# CON_ETHERNET_RJ45_LEDS.net
KiCad netlist of a schematic drawn in Altium Designer
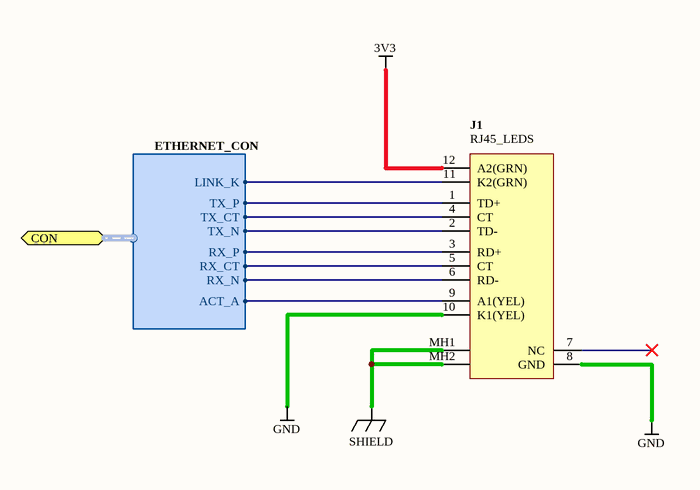
[diagram p0: CON_ETHERNET_RJ45_LEDS.SchDoc]

(export (version "E")
  (design (tool "Eeschema 10.0.6"))
  (components
    (comp (ref "J1")
      (value "RJ45_LEDS")
      (footprint "CON_RJ45_RA_LEDS")
      (description "Socket, 1x1 Tab-DOWN R/A 8-Way RJ45")
      (libsource (lib "AltiumDesignLibrary") (part "CON_RJ45_RA_LEDS"))
    )
  )
  (nets
    (net (code "2") (name "/ACT_A") (class "Default")
      (node (ref "J1") (pin "9") (pinfunction "A1(YEL)_9") (pintype "passive"))
    )
    (net (code "3") (name "/LINK_K") (class "Default")
      (node (ref "J1") (pin "11") (pinfunction "K2(GRN)_11") (pintype "passive"))
    )
    (net (code "4") (name "/RX_CT") (class "Default")
      (node (ref "J1") (pin "5") (pinfunction "CT_5") (pintype "passive"))
    )
    (net (code "5") (name "/RX_N") (class "Default")
      (node (ref "J1") (pin "6") (pinfunction "RD-_6") (pintype "passive"))
    )
    (net (code "6") (name "/RX_P") (class "Default")
      (node (ref "J1") (pin "3") (pinfunction "RD+_3") (pintype "passive"))
    )
    (net (code "7") (name "/TX_CT") (class "Default")
      (node (ref "J1") (pin "4") (pinfunction "CT_4") (pintype "passive"))
    )
    (net (code "8") (name "/TX_N") (class "Default")
      (node (ref "J1") (pin "2") (pinfunction "TD-_2") (pintype "passive"))
    )
    (net (code "9") (name "/TX_P") (class "Default")
      (node (ref "J1") (pin "1") (pinfunction "TD+_1") (pintype "passive"))
    )
    (net (code "11") (name "3V3") (class "Default")
      (node (ref "J1") (pin "12") (pinfunction "A2(GRN)_12") (pintype "passive"))
    )
    (net (code "12") (name "GND") (class "Default")
      (node (ref "J1") (pin "10") (pinfunction "K1(YEL)_10") (pintype "passive"))
      (node (ref "J1") (pin "8") (pinfunction "GND_8") (pintype "passive"))
    )
    (net (code "13") (name "SHIELD") (class "Default")
      (node (ref "J1") (pin "MH1") (pinfunction "MH1_MH1") (pintype "passive"))
      (node (ref "J1") (pin "MH2") (pinfunction "MH2_MH2") (pintype "passive"))
    )
    (net (code "14") (name "unconnected-(J1-NC-Pad7)") (class "Default")
      (node (ref "J1") (pin "7") (pinfunction "NC_7") (pintype "passive+no_connect"))
    )
  )
)
